# meroTVsensorSide.net
KiCad netlist of a schematic drawn in EAGLE
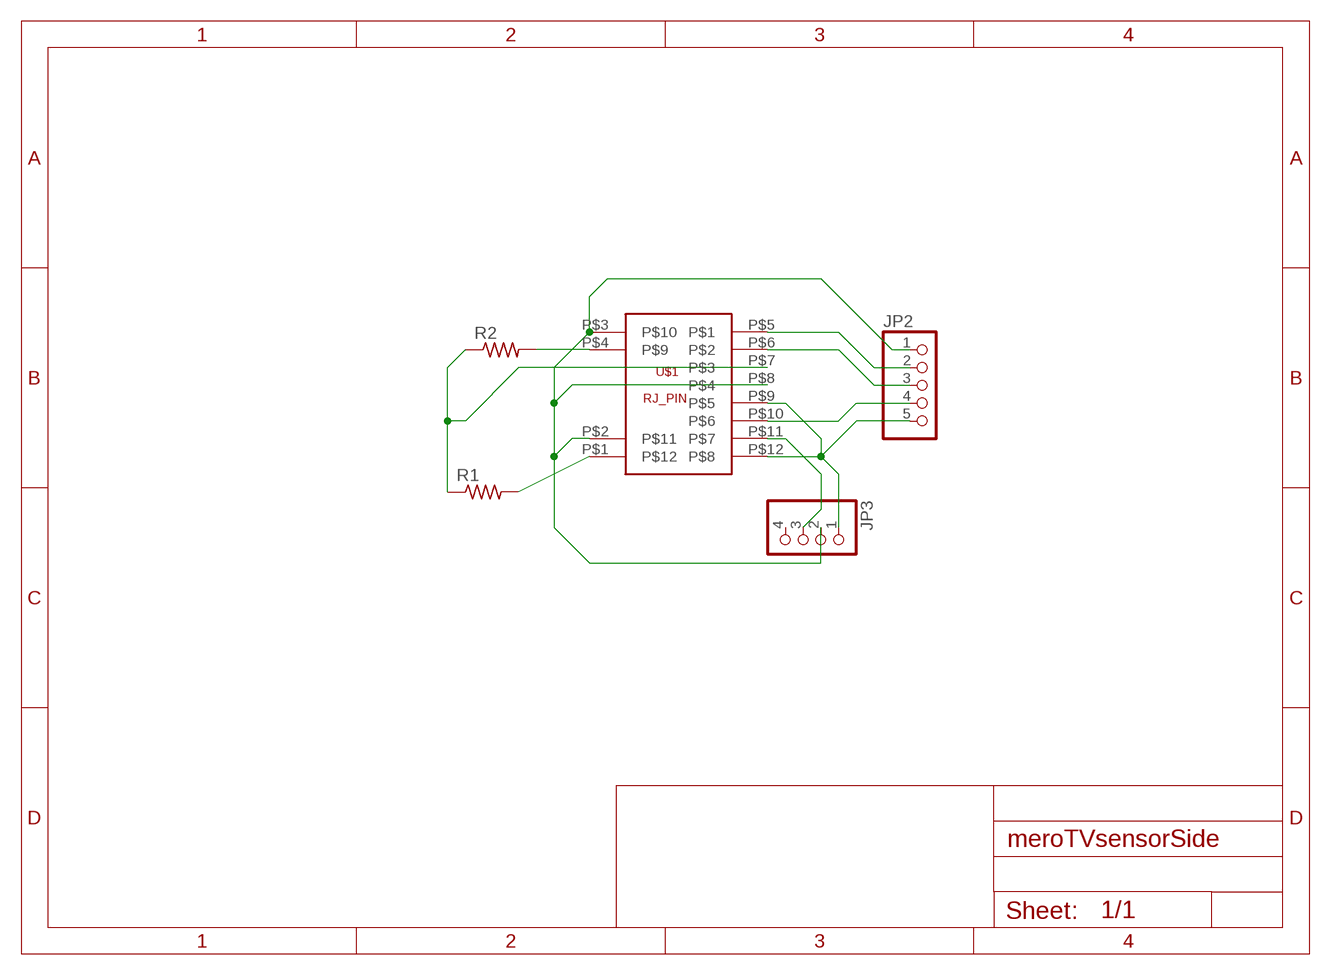
[diagram p0: schematic, sheet 1]

(export (version "E")
  (design (tool "Eeschema 10.0.6"))
  (components
    (comp (ref "JP2")
      (value "PINHD-1X5")
      (footprint "eagle-import:1X05")
      (libsource (lib "eagle-import") (part "PINHD-1X5"))
    )
    (comp (ref "JP3")
      (value "PINHD-1X4")
      (footprint "eagle-import:1X04")
      (libsource (lib "eagle-import") (part "PINHD-1X4"))
    )
    (comp (ref "R1")
      (value "R-US_0204/7")
      (footprint "eagle-import:0204_7")
      (libsource (lib "eagle-import") (part "R-US_0204/7"))
    )
    (comp (ref "R2")
      (value "R-US_0204/7")
      (footprint "eagle-import:0204_7")
      (libsource (lib "eagle-import") (part "R-US_0204/7"))
    )
    (comp (ref "U$1")
      (value "RJ45_EDWRJ45-DIL")
      (footprint "eagle-import:RJ45-DIL")
      (libsource (lib "eagle-import") (part "RJ45_EDWRJ45-DIL"))
    )
  )
  (nets
    (net (code "1") (name "Net-(U$1-P$1)") (class "Default")
      (node (ref "JP2") (pin "2") (pinfunction "2_2") (pintype "passive"))
      (node (ref "U$1") (pin "P$5") (pinfunction "P$1_P$5") (pintype "bidirectional"))
    )
    (net (code "2") (name "Net-(U$1-P$2)") (class "Default")
      (node (ref "JP2") (pin "3") (pinfunction "3_3") (pintype "passive"))
      (node (ref "U$1") (pin "P$6") (pinfunction "P$2_P$6") (pintype "bidirectional"))
    )
    (net (code "3") (name "Net-(U$1-P$3)") (class "Default")
      (node (ref "R1") (pin "1") (pinfunction "1_1") (pintype "passive"))
      (node (ref "R2") (pin "1") (pinfunction "1_1") (pintype "passive"))
      (node (ref "U$1") (pin "P$7") (pinfunction "P$3_P$7") (pintype "bidirectional"))
    )
    (net (code "4") (name "Net-(U$1-P$5)") (class "Default")
      (node (ref "JP2") (pin "5") (pinfunction "5_5") (pintype "passive"))
      (node (ref "JP3") (pin "1") (pinfunction "1_1") (pintype "passive"))
      (node (ref "U$1") (pin "P$12") (pinfunction "P$8_P$12") (pintype "bidirectional"))
      (node (ref "U$1") (pin "P$9") (pinfunction "P$5_P$9") (pintype "bidirectional"))
    )
    (net (code "5") (name "Net-(U$1-P$6)") (class "Default")
      (node (ref "JP2") (pin "4") (pinfunction "4_4") (pintype "passive"))
      (node (ref "U$1") (pin "P$10") (pinfunction "P$6_P$10") (pintype "bidirectional"))
    )
    (net (code "6") (name "Net-(U$1-P$7)") (class "Default")
      (node (ref "JP3") (pin "3") (pinfunction "3_3") (pintype "passive"))
      (node (ref "U$1") (pin "P$11") (pinfunction "P$7_P$11") (pintype "bidirectional"))
    )
    (net (code "7") (name "Net-(U$1-P$9)") (class "Default")
      (node (ref "R2") (pin "2") (pinfunction "2_2") (pintype "passive"))
      (node (ref "U$1") (pin "P$4") (pinfunction "P$9_P$4") (pintype "bidirectional"))
    )
    (net (code "8") (name "Net-(U$1-P$10)") (class "Default")
      (node (ref "JP2") (pin "1") (pinfunction "1_1") (pintype "passive"))
      (node (ref "JP3") (pin "2") (pinfunction "2_2") (pintype "passive"))
      (node (ref "U$1") (pin "P$2") (pinfunction "P$11_P$2") (pintype "bidirectional"))
      (node (ref "U$1") (pin "P$3") (pinfunction "P$10_P$3") (pintype "bidirectional"))
      (node (ref "U$1") (pin "P$8") (pinfunction "P$4_P$8") (pintype "bidirectional"))
    )
    (net (code "9") (name "Net-(U$1-P$12)") (class "Default")
      (node (ref "R1") (pin "2") (pinfunction "2_2") (pintype "passive"))
      (node (ref "U$1") (pin "P$1") (pinfunction "P$12_P$1") (pintype "bidirectional"))
    )
    (net (code "10") (name "unconnected-(JP3-Pad4)") (class "Default")
      (node (ref "JP3") (pin "4") (pinfunction "4_4") (pintype "passive"))
    )
  )
)
